# 2012_BALISE_CARTE_RECEPTEUR.net
KiCad netlist of a schematic drawn in Altium Designer
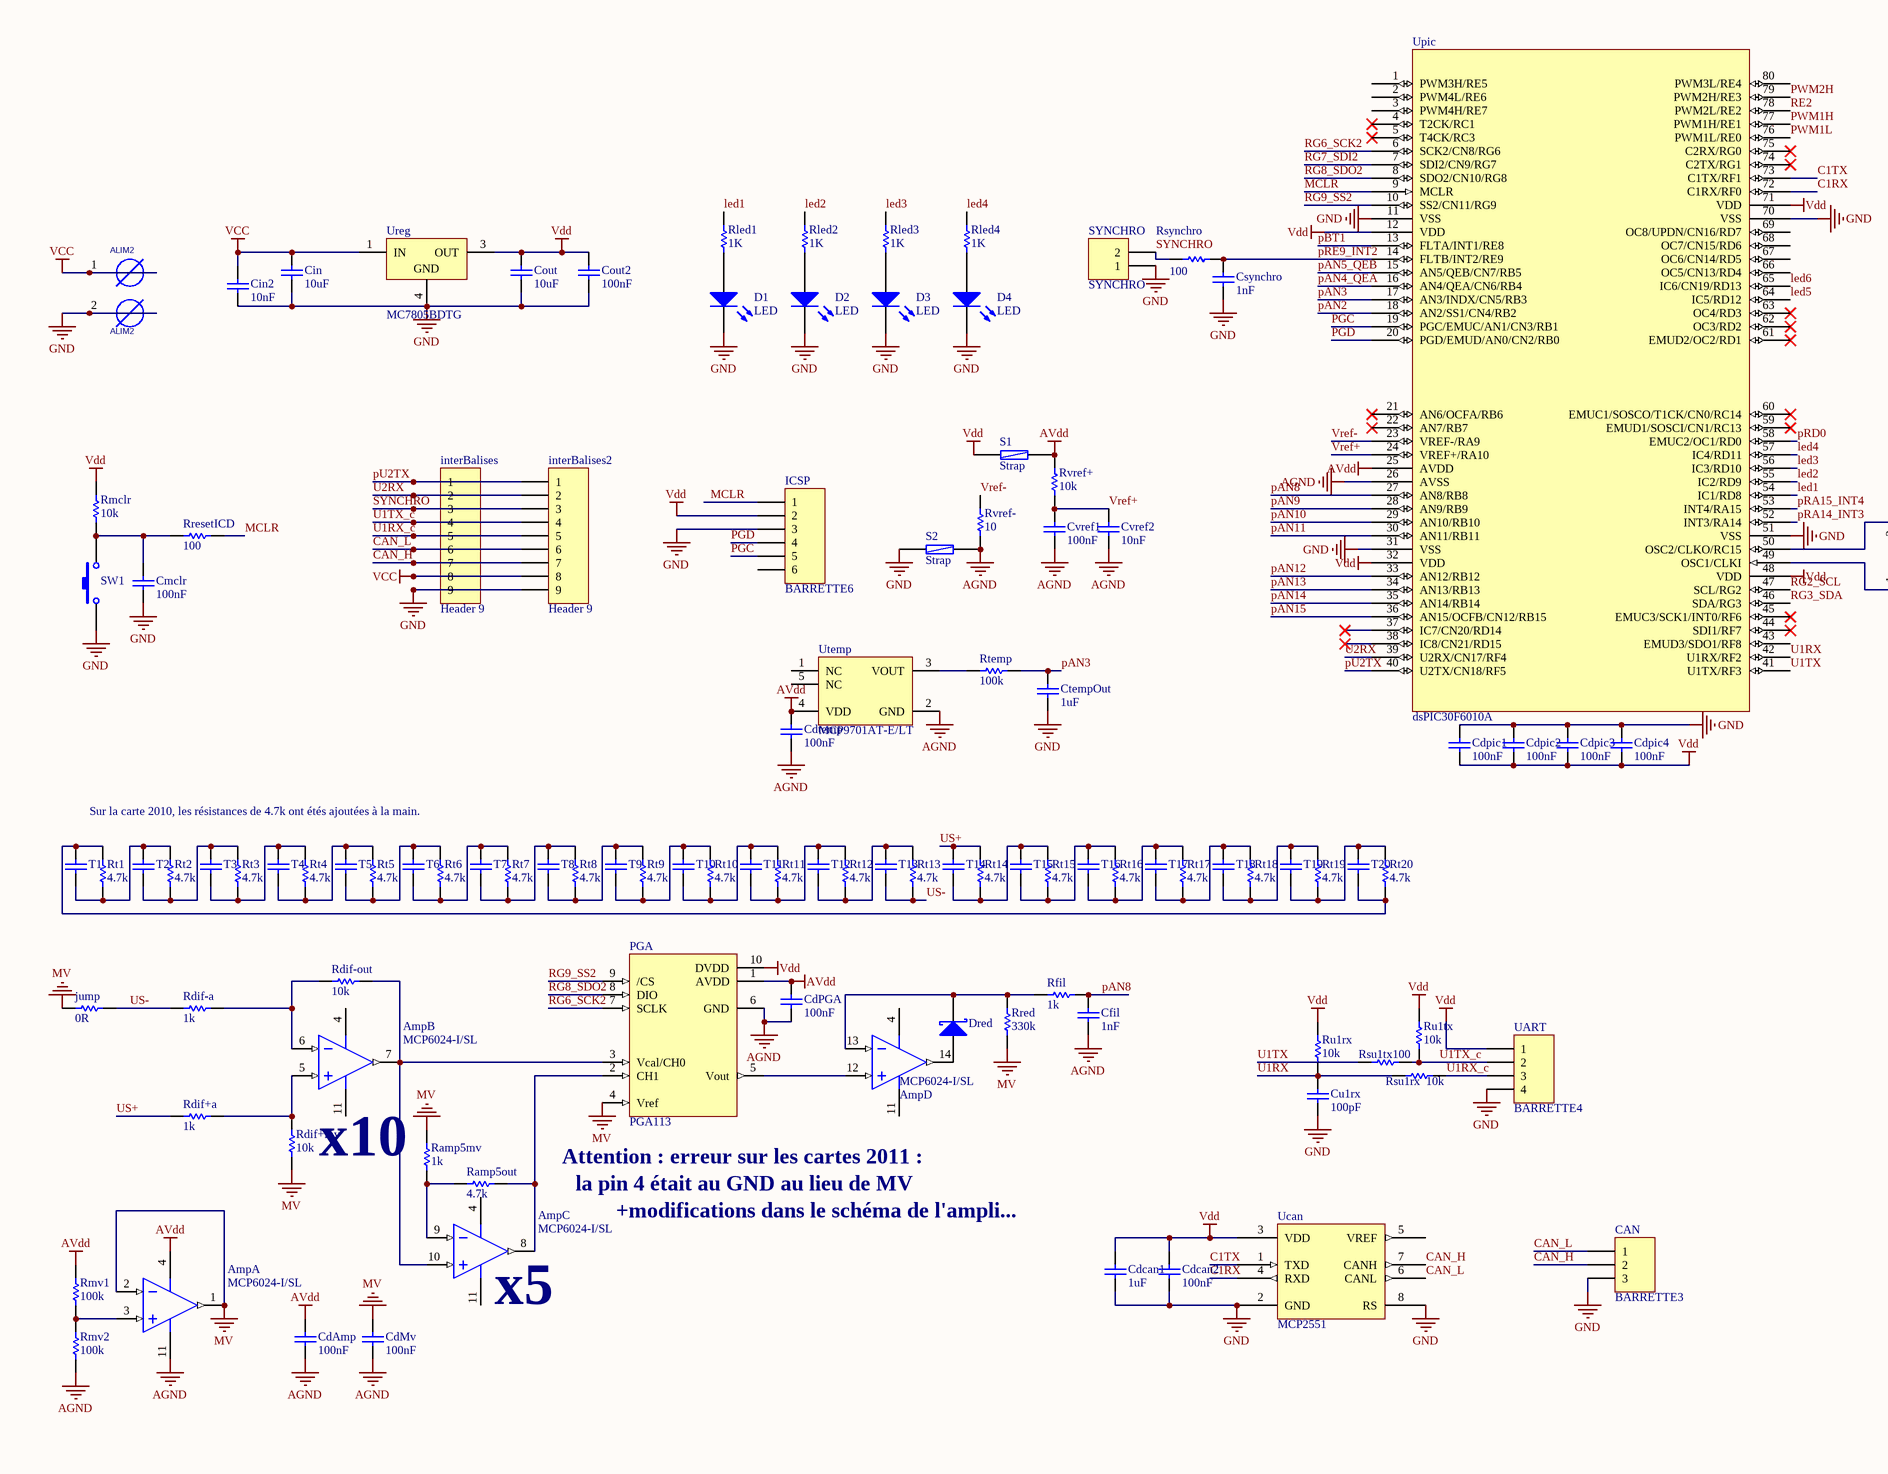
[diagram p0: 2012_BALISE_CARTE_RECEPTEUR.SchDoc, left]
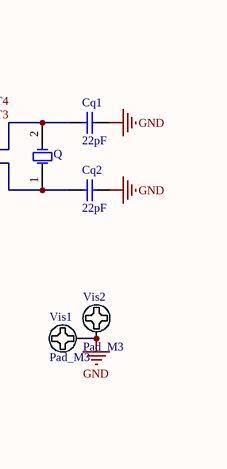
[diagram p1: 2012_BALISE_CARTE_RECEPTEUR.SchDoc, middle]
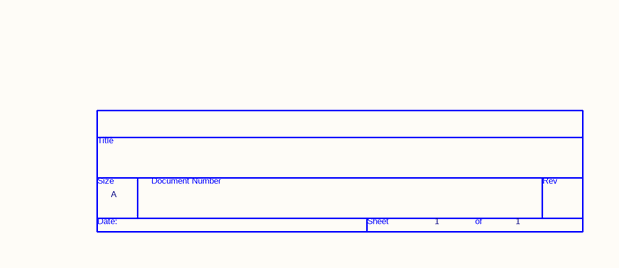
[diagram p2: 2012_BALISE_CARTE_RECEPTEUR.SchDoc, right]

(export (version "E")
  (design (tool "Eeschema 10.0.6"))
  (components
    (comp (ref "*")
      (value "TitleBlock0")
      (fields (field (name "PAGE COUNT") "1") (field (name "PAGE NUMBER") "1") (field (name "PAGE SIZE") "A"))
      (libsource (lib "*") (part "TitleBlock0"))
    )
    (comp (ref "ALIM2") (value "ALIM2") (footprint "BORNIER2") (libsource (lib "*") (part "BORNIER2")))
    (comp (ref "Amp")
      (value "MCP6024-I/SL")
      (footprint "SO14_N")
      (description "Rail-to-Rail Input/Output, 10 MHz Operational Amplifier, 14-Pin SOIC, Industrial Temperature")
      (fields (field (name "PUBLISHER") "Altium Limited"))
      (libsource (lib "Circuit intégré") (part "MCP6024-I/SL"))
    )
    (comp (ref "CAN")
      (value "BARRETTE3")
      (footprint "HE14_3")
      (description "Header, 3-Pin")
      (fields (field (name "PUBLISHER") "Altium Limited"))
      (libsource (lib "Connecteur") (part "BARRETTE3"))
    )
    (comp (ref "CdAmp")
      (value "100nF")
      (footprint "C0805_N")
      (description "Capacitor")
      (fields (field (name "PUBLISHER") "Altium Limited"))
      (libsource (lib "DG_Condensateur") (part "Capacitor"))
    )
    (comp (ref "Cdcan1")
      (value "1uF")
      (footprint "C1206_N")
      (description "Capacitor")
      (fields (field (name "PUBLISHER") "Altium Limited"))
      (libsource (lib "DG_Condensateur") (part "Capacitor"))
    )
    (comp (ref "Cdcan2")
      (value "100nF")
      (footprint "C0805_N")
      (description "Capacitor")
      (fields (field (name "PUBLISHER") "Altium Limited"))
      (libsource (lib "DG_Condensateur") (part "Capacitor"))
    )
    (comp (ref "CdMv")
      (value "100nF")
      (footprint "C0805_N")
      (description "Capacitor")
      (fields (field (name "PUBLISHER") "Altium Limited"))
      (libsource (lib "DG_Condensateur") (part "Capacitor"))
    )
    (comp (ref "CdPGA")
      (value "100nF")
      (footprint "C0805_N")
      (description "Capacitor")
      (fields (field (name "PUBLISHER") "Altium Limited"))
      (libsource (lib "DG_Condensateur") (part "Capacitor"))
    )
    (comp (ref "Cdpic1")
      (value "100nF")
      (footprint "C0805_N")
      (description "Capacitor")
      (fields (field (name "PUBLISHER") "Altium Limited"))
      (libsource (lib "DG_Condensateur") (part "Capacitor"))
    )
    (comp (ref "Cdpic2")
      (value "100nF")
      (footprint "C0805_N")
      (description "Capacitor")
      (fields (field (name "PUBLISHER") "Altium Limited"))
      (libsource (lib "DG_Condensateur") (part "Capacitor"))
    )
    (comp (ref "Cdpic3")
      (value "100nF")
      (footprint "C0805_N")
      (description "Capacitor")
      (fields (field (name "PUBLISHER") "Altium Limited"))
      (libsource (lib "DG_Condensateur") (part "Capacitor"))
    )
    (comp (ref "Cdpic4")
      (value "100nF")
      (footprint "C0805_N")
      (description "Capacitor")
      (fields (field (name "PUBLISHER") "Altium Limited"))
      (libsource (lib "DG_Condensateur") (part "Capacitor"))
    )
    (comp (ref "Cdtemp")
      (value "100nF")
      (footprint "C0805_N")
      (description "Capacitor")
      (fields (field (name "PUBLISHER") "Altium Limited"))
      (libsource (lib "DG_Condensateur") (part "Capacitor"))
    )
    (comp (ref "Cfil")
      (value "1nF")
      (footprint "C0805_N")
      (description "Capacitor")
      (fields (field (name "PUBLISHER") "Altium Limited"))
      (libsource (lib "DG_Condensateur") (part "Capacitor"))
    )
    (comp (ref "Cin")
      (value "10uF")
      (footprint "C1206_N")
      (description "Capacitor")
      (fields (field (name "PUBLISHER") "Altium Limited"))
      (libsource (lib "DG_Condensateur") (part "Capacitor"))
    )
    (comp (ref "Cin2")
      (value "10nF")
      (footprint "C0805_N")
      (description "Capacitor")
      (fields (field (name "PUBLISHER") "Altium Limited"))
      (libsource (lib "DG_Condensateur") (part "Capacitor"))
    )
    (comp (ref "Cmclr")
      (value "100nF")
      (footprint "C0805_N")
      (description "Capacitor")
      (fields (field (name "PUBLISHER") "Altium Limited"))
      (libsource (lib "DG_Condensateur") (part "Capacitor"))
    )
    (comp (ref "Cout")
      (value "10uF")
      (footprint "C1206_N")
      (description "Capacitor")
      (fields (field (name "PUBLISHER") "Altium Limited"))
      (libsource (lib "DG_Condensateur") (part "Capacitor"))
    )
    (comp (ref "Cout2")
      (value "100nF")
      (footprint "C0805_N")
      (description "Capacitor")
      (fields (field (name "PUBLISHER") "Altium Limited"))
      (libsource (lib "DG_Condensateur") (part "Capacitor"))
    )
    (comp (ref "Cq1")
      (value "22pF")
      (footprint "C0805_N")
      (description "Capacitor")
      (fields (field (name "PUBLISHER") "Altium Limited"))
      (libsource (lib "DG_Condensateur") (part "Capacitor"))
    )
    (comp (ref "Cq2")
      (value "22pF")
      (footprint "C0805_N")
      (description "Capacitor")
      (fields (field (name "PUBLISHER") "Altium Limited"))
      (libsource (lib "DG_Condensateur") (part "Capacitor"))
    )
    (comp (ref "Csynchro")
      (value "1nF")
      (footprint "C0805_N")
      (description "Capacitor")
      (fields (field (name "PUBLISHER") "Altium Limited"))
      (libsource (lib "DG_Condensateur") (part "Capacitor"))
    )
    (comp (ref "CtempOut")
      (value "1uF")
      (footprint "C0805_N")
      (description "Capacitor")
      (fields (field (name "PUBLISHER") "Altium Limited"))
      (libsource (lib "DG_Condensateur") (part "Capacitor"))
    )
    (comp (ref "Cu1rx")
      (value "100pF")
      (footprint "C0805_N")
      (description "Capacitor")
      (fields (field (name "PUBLISHER") "Altium Limited"))
      (libsource (lib "DG_Condensateur") (part "Capacitor"))
    )
    (comp (ref "Cvref1")
      (value "100nF")
      (footprint "C0805_N")
      (description "Capacitor")
      (fields (field (name "PUBLISHER") "Altium Limited"))
      (libsource (lib "DG_Condensateur") (part "Capacitor"))
    )
    (comp (ref "Cvref2")
      (value "10nF")
      (footprint "C0805_N")
      (description "Capacitor")
      (fields (field (name "PUBLISHER") "Altium Limited"))
      (libsource (lib "DG_Condensateur") (part "Capacitor"))
    )
    (comp (ref "D1")
      (value "LED")
      (footprint "LED_0805")
      (description "Typical LED")
      (fields (field (name "PUBLISHER") "Altium Limited"))
      (libsource (lib "DG_LED") (part "LED"))
    )
    (comp (ref "D2")
      (value "LED")
      (footprint "LED_0805")
      (description "Typical LED")
      (fields (field (name "PUBLISHER") "Altium Limited"))
      (libsource (lib "DG_LED") (part "LED"))
    )
    (comp (ref "D3")
      (value "LED")
      (footprint "LED_0805")
      (description "Typical LED")
      (fields (field (name "PUBLISHER") "Altium Limited"))
      (libsource (lib "DG_LED") (part "LED"))
    )
    (comp (ref "D4")
      (value "LED")
      (footprint "LED_0805")
      (description "Typical LED")
      (fields (field (name "PUBLISHER") "Altium Limited"))
      (libsource (lib "DG_LED") (part "LED"))
    )
    (comp (ref "Dred")
      (value "Diode Shottky BAT54")
      (footprint "SOT23-3N")
      (description "BAT54 - DIODE, SCHOTTKY, SOT-23")
      (fields (field (name "MANUFACTURER PART NUMBER") "BAT54"))
      (libsource (lib "_ROBOT") (part "Diode Shottky BAT54"))
    )
    (comp (ref "ICSP")
      (value "BARRETTE6")
      (footprint "HE14_6")
      (description "Header, 6-Pin")
      (fields (field (name "PUBLISHER") "Altium Limited"))
      (libsource (lib "Connecteur") (part "BARRETTE6"))
    )
    (comp (ref "interBalises")
      (value "Header 9")
      (footprint "HDR1X9")
      (description "Header, 9-Pin")
      (fields (field (name "PUBLISHER") "Altium Limited"))
      (libsource (lib "DG_Connecteur") (part "Header 9"))
    )
    (comp (ref "interBalises2")
      (value "Header 9")
      (footprint "HDR1X9")
      (description "Header, 9-Pin")
      (fields (field (name "PUBLISHER") "Altium Limited"))
      (libsource (lib "DG_Connecteur") (part "Header 9"))
    )
    (comp (ref "jump")
      (value "0R")
      (footprint "R0603_N")
      (description "Resistor")
      (fields (field (name "PUBLISHER") "Altium Limited"))
      (libsource (lib "DG_Resistance") (part "Resistor"))
    )
    (comp (ref "PGA")
      (value "PGA113")
      (footprint "MSOP-UN10_N")
      (description "Programmable Gain Amplifier")
      (libsource (lib "Circuit intégré") (part "PGA113"))
    )
    (comp (ref "Q")
      (value "QU")
      (footprint "HC49US")
      (description "Crystal Oscillator")
      (fields (field (name "PUBLISHER") "Altium Limited"))
      (libsource (lib "miniprojet") (part "QUARTZ_DROIT_BAS_PROFIL"))
    )
    (comp (ref "Ramp5mv")
      (value "1k")
      (footprint "R1206_N")
      (description "Resistor")
      (fields (field (name "PUBLISHER") "Altium Limited"))
      (libsource (lib "DG_Resistance") (part "Resistor"))
    )
    (comp (ref "Ramp5out")
      (value "4.7k")
      (footprint "R1206_N")
      (description "Resistor")
      (fields (field (name "PUBLISHER") "Altium Limited"))
      (libsource (lib "DG_Resistance") (part "Resistor"))
    )
    (comp (ref "Rdif+a")
      (value "1k")
      (footprint "R1206_N")
      (description "Resistor")
      (fields (field (name "PUBLISHER") "Altium Limited"))
      (libsource (lib "DG_Resistance") (part "Resistor"))
    )
    (comp (ref "Rdif+mv")
      (value "10k")
      (footprint "R1206_N")
      (description "Resistor")
      (fields (field (name "PUBLISHER") "Altium Limited"))
      (libsource (lib "DG_Resistance") (part "Resistor"))
    )
    (comp (ref "Rdif-a")
      (value "1k")
      (footprint "R1206_N")
      (description "Resistor")
      (fields (field (name "PUBLISHER") "Altium Limited"))
      (libsource (lib "DG_Resistance") (part "Resistor"))
    )
    (comp (ref "Rdif-out")
      (value "10k")
      (footprint "R1206_N")
      (description "Resistor")
      (fields (field (name "PUBLISHER") "Altium Limited"))
      (libsource (lib "DG_Resistance") (part "Resistor"))
    )
    (comp (ref "Rfil")
      (value "1k")
      (footprint "R1206_N")
      (description "Resistor")
      (fields (field (name "PUBLISHER") "Altium Limited"))
      (libsource (lib "DG_Resistance") (part "Resistor"))
    )
    (comp (ref "Rled1")
      (value "1K")
      (footprint "R1206_N")
      (description "Resistor")
      (fields (field (name "PUBLISHER") "Altium Limited"))
      (libsource (lib "DG_Resistance") (part "Resistor"))
    )
    (comp (ref "Rled2")
      (value "1K")
      (footprint "R1206_N")
      (description "Resistor")
      (fields (field (name "PUBLISHER") "Altium Limited"))
      (libsource (lib "DG_Resistance") (part "Resistor"))
    )
    (comp (ref "Rled3")
      (value "1K")
      (footprint "R1206_N")
      (description "Resistor")
      (fields (field (name "PUBLISHER") "Altium Limited"))
      (libsource (lib "DG_Resistance") (part "Resistor"))
    )
    (comp (ref "Rled4")
      (value "1K")
      (footprint "R1206_N")
      (description "Resistor")
      (fields (field (name "PUBLISHER") "Altium Limited"))
      (libsource (lib "DG_Resistance") (part "Resistor"))
    )
    (comp (ref "Rmclr")
      (value "10k")
      (footprint "R1206_N")
      (description "Resistor")
      (fields (field (name "PUBLISHER") "Altium Limited"))
      (libsource (lib "DG_Resistance") (part "Resistor"))
    )
    (comp (ref "Rmv1")
      (value "100k")
      (footprint "R1206_N")
      (description "Resistor")
      (fields (field (name "PUBLISHER") "Altium Limited"))
      (libsource (lib "DG_Resistance") (part "Resistor"))
    )
    (comp (ref "Rmv2")
      (value "100k")
      (footprint "R1206_N")
      (description "Resistor")
      (fields (field (name "PUBLISHER") "Altium Limited"))
      (libsource (lib "DG_Resistance") (part "Resistor"))
    )
    (comp (ref "Rred")
      (value "330k")
      (footprint "R1206_N")
      (description "Resistor")
      (fields (field (name "PUBLISHER") "Altium Limited"))
      (libsource (lib "DG_Resistance") (part "Resistor"))
    )
    (comp (ref "RresetICD")
      (value "100")
      (footprint "R1206_N")
      (description "Resistor")
      (fields (field (name "PUBLISHER") "Altium Limited"))
      (libsource (lib "DG_Resistance") (part "Resistor"))
    )
    (comp (ref "Rsu1rx")
      (value "10k")
      (footprint "R1206_N")
      (description "Resistor")
      (fields (field (name "PUBLISHER") "Altium Limited"))
      (libsource (lib "DG_Resistance") (part "Resistor"))
    )
    (comp (ref "Rsu1tx")
      (value "100")
      (footprint "R1206_N")
      (description "Resistor")
      (fields (field (name "PUBLISHER") "Altium Limited"))
      (libsource (lib "DG_Resistance") (part "Resistor"))
    )
    (comp (ref "Rsynchro")
      (value "100")
      (footprint "R1206_N")
      (description "Resistor")
      (fields (field (name "PUBLISHER") "Altium Limited"))
      (libsource (lib "_ROBOT") (part "Resistor"))
    )
    (comp (ref "Rt1")
      (value "4.7k")
      (footprint "R1206_N")
      (description "Resistor")
      (fields (field (name "PUBLISHER") "Altium Limited"))
      (libsource (lib "DG_Resistance") (part "Resistor"))
    )
    (comp (ref "Rt2")
      (value "4.7k")
      (footprint "R1206_N")
      (description "Resistor")
      (fields (field (name "PUBLISHER") "Altium Limited"))
      (libsource (lib "DG_Resistance") (part "Resistor"))
    )
    (comp (ref "Rt3")
      (value "4.7k")
      (footprint "R1206_N")
      (description "Resistor")
      (fields (field (name "PUBLISHER") "Altium Limited"))
      (libsource (lib "DG_Resistance") (part "Resistor"))
    )
    (comp (ref "Rt4")
      (value "4.7k")
      (footprint "R1206_N")
      (description "Resistor")
      (fields (field (name "PUBLISHER") "Altium Limited"))
      (libsource (lib "DG_Resistance") (part "Resistor"))
    )
    (comp (ref "Rt5")
      (value "4.7k")
      (footprint "R1206_N")
      (description "Resistor")
      (fields (field (name "PUBLISHER") "Altium Limited"))
      (libsource (lib "DG_Resistance") (part "Resistor"))
    )
    (comp (ref "Rt6")
      (value "4.7k")
      (footprint "R1206_N")
      (description "Resistor")
      (fields (field (name "PUBLISHER") "Altium Limited"))
      (libsource (lib "DG_Resistance") (part "Resistor"))
    )
    (comp (ref "Rt7")
      (value "4.7k")
      (footprint "R1206_N")
      (description "Resistor")
      (fields (field (name "PUBLISHER") "Altium Limited"))
      (libsource (lib "DG_Resistance") (part "Resistor"))
    )
    (comp (ref "Rt8")
      (value "4.7k")
      (footprint "R1206_N")
      (description "Resistor")
      (fields (field (name "PUBLISHER") "Altium Limited"))
      (libsource (lib "DG_Resistance") (part "Resistor"))
    )
    (comp (ref "Rt9")
      (value "4.7k")
      (footprint "R1206_N")
      (description "Resistor")
      (fields (field (name "PUBLISHER") "Altium Limited"))
      (libsource (lib "DG_Resistance") (part "Resistor"))
    )
    (comp (ref "Rt10")
      (value "4.7k")
      (footprint "R1206_N")
      (description "Resistor")
      (fields (field (name "PUBLISHER") "Altium Limited"))
      (libsource (lib "DG_Resistance") (part "Resistor"))
    )
    (comp (ref "Rt11")
      (value "4.7k")
      (footprint "R1206_N")
      (description "Resistor")
      (fields (field (name "PUBLISHER") "Altium Limited"))
      (libsource (lib "DG_Resistance") (part "Resistor"))
    )
    (comp (ref "Rt12")
      (value "4.7k")
      (footprint "R1206_N")
      (description "Resistor")
      (fields (field (name "PUBLISHER") "Altium Limited"))
      (libsource (lib "DG_Resistance") (part "Resistor"))
    )
    (comp (ref "Rt13")
      (value "4.7k")
      (footprint "R1206_N")
      (description "Resistor")
      (fields (field (name "PUBLISHER") "Altium Limited"))
      (libsource (lib "DG_Resistance") (part "Resistor"))
    )
    (comp (ref "Rt14")
      (value "4.7k")
      (footprint "R1206_N")
      (description "Resistor")
      (fields (field (name "PUBLISHER") "Altium Limited"))
      (libsource (lib "DG_Resistance") (part "Resistor"))
    )
    (comp (ref "Rt15")
      (value "4.7k")
      (footprint "R1206_N")
      (description "Resistor")
      (fields (field (name "PUBLISHER") "Altium Limited"))
      (libsource (lib "DG_Resistance") (part "Resistor"))
    )
    (comp (ref "Rt16")
      (value "4.7k")
      (footprint "R1206_N")
      (description "Resistor")
      (fields (field (name "PUBLISHER") "Altium Limited"))
      (libsource (lib "DG_Resistance") (part "Resistor"))
    )
    (comp (ref "Rt17")
      (value "4.7k")
      (footprint "R1206_N")
      (description "Resistor")
      (fields (field (name "PUBLISHER") "Altium Limited"))
      (libsource (lib "DG_Resistance") (part "Resistor"))
    )
    (comp (ref "Rt18")
      (value "4.7k")
      (footprint "R1206_N")
      (description "Resistor")
      (fields (field (name "PUBLISHER") "Altium Limited"))
      (libsource (lib "DG_Resistance") (part "Resistor"))
    )
    (comp (ref "Rt19")
      (value "4.7k")
      (footprint "R1206_N")
      (description "Resistor")
      (fields (field (name "PUBLISHER") "Altium Limited"))
      (libsource (lib "DG_Resistance") (part "Resistor"))
    )
    (comp (ref "Rt20")
      (value "4.7k")
      (footprint "R1206_N")
      (description "Resistor")
      (fields (field (name "PUBLISHER") "Altium Limited"))
      (libsource (lib "DG_Resistance") (part "Resistor"))
    )
    (comp (ref "Rtemp")
      (value "100k")
      (footprint "R1206_N")
      (description "Resistor")
      (fields (field (name "PUBLISHER") "Altium Limited"))
      (libsource (lib "DG_Resistance") (part "Resistor"))
    )
    (comp (ref "Ru1rx")
      (value "10k")
      (footprint "R1206_N")
      (description "Resistor")
      (fields (field (name "PUBLISHER") "Altium Limited"))
      (libsource (lib "DG_Resistance") (part "Resistor"))
    )
    (comp (ref "Ru1tx")
      (value "10k")
      (footprint "R1206_N")
      (description "Resistor")
      (fields (field (name "PUBLISHER") "Altium Limited"))
      (libsource (lib "DG_Resistance") (part "Resistor"))
    )
    (comp (ref "Rvref+")
      (value "10k")
      (footprint "R1206_N")
      (description "Resistor")
      (fields (field (name "PUBLISHER") "Altium Limited"))
      (libsource (lib "DG_Resistance") (part "Resistor"))
    )
    (comp (ref "Rvref-")
      (value "10")
      (footprint "R1206_N")
      (description "Resistor")
      (fields (field (name "PUBLISHER") "Altium Limited"))
      (libsource (lib "DG_Resistance") (part "Resistor"))
    )
    (comp (ref "S1")
      (value "Strap")
      (footprint "R0805_N")
      (description "Fuse")
      (fields (field (name "PUBLISHER") "Altium Limited"))
      (libsource (lib "_ROBOT") (part "Fusible_SMD"))
    )
    (comp (ref "S2")
      (value "Strap")
      (footprint "R0805_N")
      (description "Fuse")
      (fields (field (name "PUBLISHER") "Altium Limited"))
      (libsource (lib "_ROBOT") (part "Fusible_SMD"))
    )
    (comp (ref "SW1")
      (value "SW_Pushbutton_6x6mm_Vertical")
      (footprint "Switch 6x6 Vertical")
      (description "Switch tactil 6mm x 6mm Vertical")
      (fields (field (name "PUBLISHER") "Damien Guitton"))
      (libsource (lib "DG_Interrupteur") (part "SW_Pushbutton_6x6mm_Vertical"))
    )
    (comp (ref "SYNCHRO")
      (value "SYNCHRO")
      (footprint "Robot2010:HEADER2")
      (description "Header, 2-Pin")
      (fields (field (name "PUBLISHER") "Altium Limited"))
      (libsource (lib "Robot2010") (part "BARRETTE2"))
    )
    (comp (ref "T1")
      (value "40kHz")
      (footprint "MA40S4R/S Transducteur US - 3D_mi_carte")
      (description "Capacitor")
      (fields (field (name "PUBLISHER") "Altium Limited"))
      (libsource (lib "_ROBOT") (part "Condensateur"))
    )
    (comp (ref "T2")
      (value "40kHz")
      (footprint "MA40S4R/S Transducteur US - 3D_mi_carte")
      (description "Capacitor")
      (fields (field (name "PUBLISHER") "Altium Limited"))
      (libsource (lib "_ROBOT") (part "Condensateur"))
    )
    (comp (ref "T3")
      (value "40kHz")
      (footprint "MA40S4R/S Transducteur US - 3D_mi_carte")
      (description "Capacitor")
      (fields (field (name "PUBLISHER") "Altium Limited"))
      (libsource (lib "_ROBOT") (part "Condensateur"))
    )
    (comp (ref "T4")
      (value "40kHz")
      (footprint "MA40S4R/S Transducteur US - 3D_mi_carte")
      (description "Capacitor")
      (fields (field (name "PUBLISHER") "Altium Limited"))
      (libsource (lib "_ROBOT") (part "Condensateur"))
    )
    (comp (ref "T5")
      (value "40kHz")
      (footprint "MA40S4R/S Transducteur US - 3D_mi_carte")
      (description "Capacitor")
      (fields (field (name "PUBLISHER") "Altium Limited"))
      (libsource (lib "_ROBOT") (part "Condensateur"))
    )
    (comp (ref "T6")
      (value "40kHz")
      (footprint "MA40S4R/S Transducteur US - 3D_mi_carte")
      (description "Capacitor")
      (fields (field (name "PUBLISHER") "Altium Limited"))
      (libsource (lib "_ROBOT") (part "Condensateur"))
    )
    (comp (ref "T7")
      (value "40kHz")
      (footprint "MA40S4R/S Transducteur US - 3D_mi_carte")
      (description "Capacitor")
      (fields (field (name "PUBLISHER") "Altium Limited"))
      (libsource (lib "_ROBOT") (part "Condensateur"))
    )
    (comp (ref "T8")
      (value "40kHz")
      (footprint "MA40S4R/S Transducteur US - 3D_mi_carte")
      (description "Capacitor")
      (fields (field (name "PUBLISHER") "Altium Limited"))
      (libsource (lib "_ROBOT") (part "Condensateur"))
    )
    (comp (ref "T9")
      (value "40kHz")
      (footprint "MA40S4R/S Transducteur US - 3D_mi_carte")
      (description "Capacitor")
      (fields (field (name "PUBLISHER") "Altium Limited"))
      (libsource (lib "_ROBOT") (part "Condensateur"))
    )
    (comp (ref "T10")
      (value "40kHz")
      (footprint "MA40S4R/S Transducteur US - 3D_mi_carte")
      (description "Capacitor")
      (fields (field (name "PUBLISHER") "Altium Limited"))
      (libsource (lib "_ROBOT") (part "Condensateur"))
    )
    (comp (ref "T11")
      (value "40kHz")
      (footprint "MA40S4R/S Transducteur US - 3D_mi_carte")
      (description "Capacitor")
      (fields (field (name "PUBLISHER") "Altium Limited"))
      (libsource (lib "_ROBOT") (part "Condensateur"))
    )
    (comp (ref "T12")
      (value "40kHz")
      (footprint "MA40S4R/S Transducteur US - 3D_mi_carte")
      (description "Capacitor")
      (fields (field (name "PUBLISHER") "Altium Limited"))
      (libsource (lib "_ROBOT") (part "Condensateur"))
    )
    (comp (ref "T13")
      (value "40kHz")
      (footprint "MA40S4R/S Transducteur US - 3D_mi_carte")
      (description "Capacitor")
      (fields (field (name "PUBLISHER") "Altium Limited"))
      (libsource (lib "_ROBOT") (part "Condensateur"))
    )
    (comp (ref "T14")
      (value "40kHz")
      (footprint "MA40S4R/S Transducteur US - 3D_mi_carte")
      (description "Capacitor")
      (fields (field (name "PUBLISHER") "Altium Limited"))
      (libsource (lib "_ROBOT") (part "Condensateur"))
    )
    (comp (ref "T15")
      (value "40kHz")
      (footprint "MA40S4R/S Transducteur US - 3D_mi_carte")
      (description "Capacitor")
      (fields (field (name "PUBLISHER") "Altium Limited"))
      (libsource (lib "_ROBOT") (part "Condensateur"))
    )
    (comp (ref "T16")
      (value "40kHz")
      (footprint "MA40S4R/S Transducteur US - 3D_mi_carte")
      (description "Capacitor")
      (fields (field (name "PUBLISHER") "Altium Limited"))
      (libsource (lib "_ROBOT") (part "Condensateur"))
    )
    (comp (ref "T17")
      (value "40kHz")
      (footprint "MA40S4R/S Transducteur US - 3D_mi_carte")
      (description "Capacitor")
      (fields (field (name "PUBLISHER") "Altium Limited"))
      (libsource (lib "_ROBOT") (part "Condensateur"))
    )
    (comp (ref "T18")
      (value "40kHz")
      (footprint "MA40S4R/S Transducteur US - 3D_mi_carte")
      (description "Capacitor")
      (fields (field (name "PUBLISHER") "Altium Limited"))
      (libsource (lib "_ROBOT") (part "Condensateur"))
    )
    (comp (ref "T19")
      (value "40kHz")
      (footprint "MA40S4R/S Transducteur US - 3D_mi_carte")
      (description "Capacitor")
      (fields (field (name "PUBLISHER") "Altium Limited"))
      (libsource (lib "_ROBOT") (part "Condensateur"))
    )
    (comp (ref "T20")
      (value "40kHz")
      (footprint "MA40S4R/S Transducteur US - 3D_mi_carte")
      (description "Capacitor")
      (fields (field (name "PUBLISHER") "Altium Limited"))
      (libsource (lib "_ROBOT") (part "Condensateur"))
    )
    (comp (ref "UART")
      (value "BARRETTE4")
      (footprint "HE14_4")
      (description "Header, 4-Pin")
      (fields (field (name "PUBLISHER") "Altium Limited"))
      (libsource (lib "Connecteur") (part "BARRETTE4"))
    )
    (comp (ref "Ucan")
      (value "MCP2551")
      (footprint "SO8_N")
      (description "High Speed Can Transceiver")
      (fields (field (name "PUBLISHER") "Altium Limited"))
      (libsource (lib "Microchip Interface Line Transceiver") (part "MCP2551"))
    )
    (comp (ref "Upic")
      (value "dsPIC30F6010A")
      (footprint "TQFP80_N")
      (description "High-Performance, 16-bit Digital Signal Controllers")
      (libsource (lib "DG_Microcontroleur") (part "dsPIC30F6010A"))
    )
    (comp (ref "Ureg")
      (value "MC7805BDTG")
      (footprint "369A-13")
      (description "Three-Terminal Positive Voltage Regulator")
      (fields (field (name "PUBLISHER") "Altium Limited"))
      (libsource (lib "ON Semi Power Mgt Voltage Regulator") (part "MC7805ACD2T"))
    )
    (comp (ref "Utemp")
      (value "MCP9701AT-E/LT")
      (footprint "SC70-LT5_N")
      (description "Low-Power Linear Active Thermistor IC, 5-Pin SC-70, Extended Temperature, Tape and Reel")
      (fields (field (name "PUBLISHER") "Altium Limited"))
      (libsource (lib "Microchip Thermal Management") (part "MCP9701AT-E/LT"))
    )
    (comp (ref "Vis1")
      (value "Pad_M3")
      (footprint "M3x6mm")
      (description "Vis M3 X 6mm _TORX_Tête 6mm")
      (fields (field (name "PUBLISHER") "Damien Guitton"))
      (libsource (lib "DG_Mecanique") (part "Vis M3 X 6mm _TORX_Tête 6mm"))
    )
    (comp (ref "Vis2")
      (value "Pad_M3")
      (footprint "M3x6mm")
      (description "Vis M3 X 6mm _TORX_Tête 6mm")
      (fields (field (name "PUBLISHER") "Damien Guitton"))
      (libsource (lib "DG_Mecanique") (part "Vis M3 X 6mm _TORX_Tête 6mm"))
    )
  )
  (nets
    (net (code "1") (name "/C1RX") (class "Default")
      (node (ref "Ucan") (pin "4") (pinfunction "RXD_4") (pintype "output"))
      (node (ref "Upic") (pin "72") (pinfunction "C1RX/RF0_72") (pintype "bidirectional"))
    )
    (net (code "2") (name "/C1TX") (class "Default")
      (node (ref "Ucan") (pin "1") (pinfunction "TXD_1") (pintype "input"))
      (node (ref "Upic") (pin "73") (pinfunction "C1TX/RF1_73") (pintype "bidirectional"))
    )
    (net (code "3") (name "/CAN_H") (class "Default")
      (node (ref "CAN") (pin "2") (pinfunction "2_2") (pintype "passive"))
      (node (ref "Ucan") (pin "7") (pinfunction "CANH_7") (pintype "output"))
      (node (ref "interBalises") (pin "7") (pinfunction "7_7") (pintype "passive"))
      (node (ref "interBalises2") (pin "7") (pinfunction "7_7") (pintype "passive"))
    )
    (net (code "4") (name "/CAN_L") (class "Default")
      (node (ref "CAN") (pin "1") (pinfunction "1_1") (pintype "passive"))
      (node (ref "Ucan") (pin "6") (pinfunction "CANL_6") (pintype "output"))
      (node (ref "interBalises") (pin "6") (pinfunction "6_6") (pintype "passive"))
      (node (ref "interBalises2") (pin "6") (pinfunction "6_6") (pintype "passive"))
    )
    (net (code "5") (name "/MCLR") (class "Default")
      (node (ref "ICSP") (pin "1") (pinfunction "1_1") (pintype "passive"))
      (node (ref "RresetICD") (pin "1") (pinfunction "1_1") (pintype "passive"))
      (node (ref "Upic") (pin "9") (pinfunction "MCLR_9") (pintype "input"))
    )
    (net (code "6") (name "/PGC") (class "Default")
      (node (ref "ICSP") (pin "5") (pinfunction "5_5") (pintype "passive"))
      (node (ref "Upic") (pin "19") (pinfunction "PGC/EMUC/AN1/CN3/RB1_19") (pintype "bidirectional"))
    )
    (net (code "7") (name "/PGD") (class "Default")
      (node (ref "ICSP") (pin "4") (pinfunction "4_4") (pintype "passive"))
      (node (ref "Upic") (pin "20") (pinfunction "PGD/EMUD/AN0/CN2/RB0_20") (pintype "bidirectional"))
    )
    (net (code "8") (name "/PWM1H") (class "Default")
      (node (ref "Upic") (pin "77") (pinfunction "PWM1H/RE1_77") (pintype "bidirectional"))
    )
    (net (code "9") (name "/PWM1L") (class "Default")
      (node (ref "Upic") (pin "76") (pinfunction "PWM1L/RE0_76") (pintype "bidirectional"))
    )
    (net (code "10") (name "/PWM2H") (class "Default")
      (node (ref "Upic") (pin "79") (pinfunction "PWM2H/RE3_79") (pintype "bidirectional"))
    )
    (net (code "11") (name "/RE2") (class "Default")
      (node (ref "Upic") (pin "78") (pinfunction "PWM2L/RE2_78") (pintype "bidirectional"))
    )
    (net (code "12") (name "/RG2_SCL") (class "Default")
      (node (ref "Upic") (pin "47") (pinfunction "SCL/RG2_47") (pintype "bidirectional"))
    )
    (net (code "13") (name "/RG3_SDA") (class "Default")
      (node (ref "Upic") (pin "46") (pinfunction "SDA/RG3_46") (pintype "bidirectional"))
    )
    (net (code "14") (name "/RG6_SCK2") (class "Default")
      (node (ref "PGA") (pin "7") (pinfunction "SCLK_7") (pintype "input"))
      (node (ref "Upic") (pin "6") (pinfunction "SCK2/CN8/RG6_6") (pintype "bidirectional"))
    )
    (net (code "15") (name "/RG7_SDI2") (class "Default")
      (node (ref "Upic") (pin "7") (pinfunction "SDI2/CN9/RG7_7") (pintype "bidirectional"))
    )
    (net (code "16") (name "/RG8_SDO2") (class "Default")
      (node (ref "PGA") (pin "8") (pinfunction "DIO_8") (pintype "input"))
      (node (ref "Upic") (pin "8") (pinfunction "SDO2/CN10/RG8_8") (pintype "bidirectional"))
    )
    (net (code "17") (name "/RG9_SS2") (class "Default")
      (node (ref "PGA") (pin "9") (pinfunction "/CS_9") (pintype "input"))
      (node (ref "Upic") (pin "10") (pinfunction "SS2/CN11/RG9_10") (pintype "bidirectional"))
    )
    (net (code "18") (name "/SYNCHRO") (class "Default")
      (node (ref "Rsynchro") (pin "1") (pinfunction "1_1") (pintype "passive"))
      (node (ref "SYNCHRO") (pin "2") (pinfunction "2_2") (pintype "passive"))
      (node (ref "interBalises") (pin "3") (pinfunction "3_3") (pintype "passive"))
      (node (ref "interBalises2") (pin "3") (pinfunction "3_3") (pintype "passive"))
    )
    (net (code "19") (name "/U1RX") (class "Default")
      (node (ref "Cu1rx") (pin "2") (pinfunction "2_2") (pintype "passive"))
      (node (ref "Rsu1rx") (pin "2") (pinfunction "2_2") (pintype "passive"))
      (node (ref "Ru1rx") (pin "1") (pinfunction "1_1") (pintype "passive"))
      (node (ref "Upic") (pin "42") (pinfunction "U1RX/RF2_42") (pintype "bidirectional"))
    )
    (net (code "20") (name "/U1RX_c") (class "Default")
      (node (ref "Rsu1rx") (pin "1") (pinfunction "1_1") (pintype "passive"))
      (node (ref "UART") (pin "3") (pinfunction "3_3") (pintype "passive"))
      (node (ref "interBalises") (pin "5") (pinfunction "5_5") (pintype "passive"))
      (node (ref "interBalises2") (pin "5") (pinfunction "5_5") (pintype "passive"))
    )
    (net (code "21") (name "/U1TX") (class "Default")
      (node (ref "Rsu1tx") (pin "2") (pinfunction "2_2") (pintype "passive"))
      (node (ref "Upic") (pin "41") (pinfunction "U1TX/RF3_41") (pintype "bidirectional"))
    )
    (net (code "22") (name "/U1TX_c") (class "Default")
      (node (ref "Rsu1tx") (pin "1") (pinfunction "1_1") (pintype "passive"))
      (node (ref "Ru1tx") (pin "1") (pinfunction "1_1") (pintype "passive"))
      (node (ref "UART") (pin "2") (pinfunction "2_2") (pintype "passive"))
      (node (ref "interBalises") (pin "4") (pinfunction "4_4") (pintype "passive"))
      (node (ref "interBalises2") (pin "4") (pinfunction "4_4") (pintype "passive"))
    )
    (net (code "23") (name "/U2RX") (class "Default")
      (node (ref "Upic") (pin "39") (pinfunction "U2RX/CN17/RF4_39") (pintype "bidirectional"))
      (node (ref "interBalises") (pin "2") (pinfunction "2_2") (pintype "passive"))
      (node (ref "interBalises2") (pin "2") (pinfunction "2_2") (pintype "passive"))
    )
    (net (code "24") (name "/US+") (class "Default")
      (node (ref "Rdif+a") (pin "2") (pinfunction "2_2") (pintype "passive"))
      (node (ref "Rt14") (pin "1") (pinfunction "1_1") (pintype "passive"))
      (node (ref "T14") (pin "2") (pinfunction "2_2") (pintype "passive"))
    )
    (net (code "25") (name "/US-") (class "Default")
      (node (ref "Rdif-a") (pin "2") (pinfunction "2_2") (pintype "passive"))
      (node (ref "Rt13") (pin "2") (pinfunction "2_2") (pintype "passive"))
      (node (ref "T13") (pin "1") (pinfunction "1_1") (pintype "passive"))
      (node (ref "jump") (pin "2") (pinfunction "2_2") (pintype "passive"))
    )
    (net (code "26") (name "/Vref+") (class "Default")
      (node (ref "Cvref1") (pin "2") (pinfunction "2_2") (pintype "passive"))
      (node (ref "Cvref2") (pin "2") (pinfunction "2_2") (pintype "passive"))
      (node (ref "Rvref+") (pin "1") (pinfunction "1_1") (pintype "passive"))
      (node (ref "Upic") (pin "24") (pinfunction "VREF+/RA10_24") (pintype "bidirectional"))
    )
    (net (code "27") (name "/Vref-") (class "Default")
      (node (ref "Rvref-") (pin "2") (pinfunction "2_2") (pintype "passive"))
      (node (ref "Upic") (pin "23") (pinfunction "VREF-/RA9_23") (pintype "bidirectional"))
    )
    (net (code "28") (name "/led1") (class "Default")
      (node (ref "Rled1") (pin "2") (pinfunction "2_2") (pintype "passive"))
      (node (ref "Upic") (pin "54") (pinfunction "IC1/RD8_54") (pintype "bidirectional"))
    )
    (net (code "29") (name "/led2") (class "Default")
      (node (ref "Rled2") (pin "2") (pinfunction "2_2") (pintype "passive"))
      (node (ref "Upic") (pin "55") (pinfunction "IC2/RD9_55") (pintype "bidirectional"))
    )
    (net (code "30") (name "/led3") (class "Default")
      (node (ref "Rled3") (pin "2") (pinfunction "2_2") (pintype "passive"))
      (node (ref "Upic") (pin "56") (pinfunction "IC3/RD10_56") (pintype "bidirectional"))
    )
    (net (code "31") (name "/led4") (class "Default")
      (node (ref "Rled4") (pin "2") (pinfunction "2_2") (pintype "passive"))
      (node (ref "Upic") (pin "57") (pinfunction "IC4/RD11_57") (pintype "bidirectional"))
    )
    (net (code "32") (name "/led5") (class "Default")
      (node (ref "Upic") (pin "64") (pinfunction "IC5/RD12_64") (pintype "bidirectional"))
    )
    (net (code "33") (name "/led6") (class "Default")
      (node (ref "Upic") (pin "65") (pinfunction "IC6/CN19/RD13_65") (pintype "bidirectional"))
    )
    (net (code "34") (name "/pAN2") (class "Default")
      (node (ref "Upic") (pin "18") (pinfunction "AN2/SS1/CN4/RB2_18") (pintype "bidirectional"))
    )
    (net (code "35") (name "/pAN3") (class "Default")
      (node (ref "CtempOut") (pin "2") (pinfunction "2_2") (pintype "passive"))
      (node (ref "Rtemp") (pin "1") (pinfunction "1_1") (pintype "passive"))
      (node (ref "Upic") (pin "17") (pinfunction "AN3/INDX/CN5/RB3_17") (pintype "bidirectional"))
    )
    (net (code "36") (name "/pAN4_QEA") (class "Default")
      (node (ref "Upic") (pin "16") (pinfunction "AN4/QEA/CN6/RB4_16") (pintype "bidirectional"))
    )
    (net (code "37") (name "/pAN5_QEB") (class "Default")
      (node (ref "Upic") (pin "15") (pinfunction "AN5/QEB/CN7/RB5_15") (pintype "bidirectional"))
    )
    (net (code "38") (name "/pAN8") (class "Default")
      (node (ref "Cfil") (pin "2") (pinfunction "2_2") (pintype "passive"))
      (node (ref "Rfil") (pin "2") (pinfunction "2_2") (pintype "passive"))
      (node (ref "Upic") (pin "27") (pinfunction "AN8/RB8_27") (pintype "bidirectional"))
    )
    (net (code "39") (name "/pAN9") (class "Default")
      (node (ref "Upic") (pin "28") (pinfunction "AN9/RB9_28") (pintype "bidirectional"))
    )
    (net (code "40") (name "/pAN10") (class "Default")
      (node (ref "Upic") (pin "29") (pinfunction "AN10/RB10_29") (pintype "bidirectional"))
    )
    (net (code "41") (name "/pAN11") (class "Default")
      (node (ref "Upic") (pin "30") (pinfunction "AN11/RB11_30") (pintype "bidirectional"))
    )
    (net (code "42") (name "/pAN12") (class "Default")
      (node (ref "Upic") (pin "33") (pinfunction "AN12/RB12_33") (pintype "bidirectional"))
    )
    (net (code "43") (name "/pAN13") (class "Default")
      (node (ref "Upic") (pin "34") (pinfunction "AN13/RB13_34") (pintype "bidirectional"))
    )
    (net (code "44") (name "/pAN14") (class "Default")
      (node (ref "Upic") (pin "35") (pinfunction "AN14/RB14_35") (pintype "bidirectional"))
    )
    (net (code "45") (name "/pAN15") (class "Default")
      (node (ref "Upic") (pin "36") (pinfunction "AN15/OCFB/CN12/RB15_36") (pintype "bidirectional"))
    )
    (net (code "46") (name "/pBT1") (class "Default")
      (node (ref "Upic") (pin "13") (pinfunction "FLTA/INT1/RE8_13") (pintype "bidirectional"))
    )
    (net (code "47") (name "/pRA14_INT3") (class "Default")
      (node (ref "Upic") (pin "52") (pinfunction "INT3/RA14_52") (pintype "bidirectional"))
    )
    (net (code "48") (name "/pRA15_INT4") (class "Default")
      (node (ref "Upic") (pin "53") (pinfunction "INT4/RA15_53") (pintype "bidirectional"))
    )
    (net (code "49") (name "/pRD0") (class "Default")
      (node (ref "Upic") (pin "58") (pinfunction "EMUC2/OC1/RD0_58") (pintype "bidirectional"))
    )
    (net (code "50") (name "/pRE9_INT2") (class "Default")
      (node (ref "Csynchro") (pin "1") (pinfunction "1_1") (pintype "passive"))
      (node (ref "Rsynchro") (pin "2") (pinfunction "2_2") (pintype "passive"))
      (node (ref "Upic") (pin "14") (pinfunction "FLTB/INT2/RE9_14") (pintype "bidirectional"))
    )
    (net (code "51") (name "/pU2TX") (class "Default")
      (node (ref "Upic") (pin "40") (pinfunction "U2TX/CN18/RF5_40") (pintype "bidirectional"))
      (node (ref "interBalises") (pin "1") (pinfunction "1_1") (pintype "passive"))
      (node (ref "interBalises2") (pin "1") (pinfunction "1_1") (pintype "passive"))
    )
    (net (code "52") (name "AGND") (class "Default")
      (node (ref "Amp") (pin "11") (pinfunction "VSS_11") (pintype "power_in"))
      (node (ref "CdAmp") (pin "1") (pinfunction "1_1") (pintype "passive"))
      (node (ref "CdMv") (pin "1") (pinfunction "1_1") (pintype "passive"))
      (node (ref "CdPGA") (pin "1") (pinfunction "1_1") (pintype "passive"))
      (node (ref "Cdtemp") (pin "1") (pinfunction "1_1") (pintype "passive"))
      (node (ref "Cfil") (pin "1") (pinfunction "1_1") (pintype "passive"))
      (node (ref "Cvref1") (pin "1") (pinfunction "1_1") (pintype "passive"))
      (node (ref "Cvref2") (pin "1") (pinfunction "1_1") (pintype "passive"))
      (node (ref "PGA") (pin "6") (pinfunction "GND_6") (pintype "power_in"))
      (node (ref "Rmv2") (pin "1") (pinfunction "1_1") (pintype "passive"))
      (node (ref "Rvref-") (pin "1") (pinfunction "1_1") (pintype "passive"))
      (node (ref "S2") (pin "2") (pinfunction "2_2") (pintype "passive"))
      (node (ref "Upic") (pin "26") (pinfunction "AVSS_26") (pintype "power_in"))
      (node (ref "Utemp") (pin "2") (pinfunction "GND_2") (pintype "power_in"))
    )
    (net (code "53") (name "AVdd") (class "Default")
      (node (ref "Amp") (pin "4") (pinfunction "VDD_4") (pintype "power_in"))
      (node (ref "CdAmp") (pin "2") (pinfunction "2_2") (pintype "passive"))
      (node (ref "CdPGA") (pin "2") (pinfunction "2_2") (pintype "passive"))
      (node (ref "Cdtemp") (pin "2") (pinfunction "2_2") (pintype "passive"))
      (node (ref "PGA") (pin "1") (pinfunction "AVDD_1") (pintype "power_in"))
      (node (ref "Rmv1") (pin "2") (pinfunction "2_2") (pintype "passive"))
      (node (ref "Rvref+") (pin "2") (pinfunction "2_2") (pintype "passive"))
      (node (ref "S1") (pin "2") (pinfunction "2_2") (pintype "passive"))
      (node (ref "Upic") (pin "25") (pinfunction "AVDD_25") (pintype "power_in"))
      (node (ref "Utemp") (pin "4") (pinfunction "VDD_4") (pintype "power_in"))
    )
    (net (code "54") (name "GND") (class "Default")
      (node (ref "ALIM2") (pin "2") (pinfunction "B2_2") (pintype "passive"))
      (node (ref "CAN") (pin "3") (pinfunction "3_3") (pintype "passive"))
      (node (ref "Cdcan1") (pin "1") (pinfunction "1_1") (pintype "passive"))
      (node (ref "Cdcan2") (pin "1") (pinfunction "1_1") (pintype "passive"))
      (node (ref "Cdpic1") (pin "2") (pinfunction "2_2") (pintype "passive"))
      (node (ref "Cdpic2") (pin "2") (pinfunction "2_2") (pintype "passive"))
      (node (ref "Cdpic3") (pin "2") (pinfunction "2_2") (pintype "passive"))
      (node (ref "Cdpic4") (pin "2") (pinfunction "2_2") (pintype "passive"))
      (node (ref "Cin") (pin "1") (pinfunction "1_1") (pintype "passive"))
      (node (ref "Cin2") (pin "1") (pinfunction "1_1") (pintype "passive"))
      (node (ref "Cmclr") (pin "1") (pinfunction "1_1") (pintype "passive"))
      (node (ref "Cout") (pin "1") (pinfunction "1_1") (pintype "passive"))
      (node (ref "Cout2") (pin "1") (pinfunction "1_1") (pintype "passive"))
      (node (ref "Cq1") (pin "2") (pinfunction "2_2") (pintype "passive"))
      (node (ref "Cq2") (pin "2") (pinfunction "2_2") (pintype "passive"))
      (node (ref "Csynchro") (pin "2") (pinfunction "2_2") (pintype "passive"))
      (node (ref "CtempOut") (pin "1") (pinfunction "1_1") (pintype "passive"))
      (node (ref "Cu1rx") (pin "1") (pinfunction "1_1") (pintype "passive"))
      (node (ref "D1") (pin "2") (pinfunction "2_2") (pintype "passive"))
      (node (ref "D2") (pin "2") (pinfunction "2_2") (pintype "passive"))
      (node (ref "D3") (pin "2") (pinfunction "2_2") (pintype "passive"))
      (node (ref "D4") (pin "2") (pinfunction "2_2") (pintype "passive"))
      (node (ref "ICSP") (pin "3") (pinfunction "3_3") (pintype "passive"))
      (node (ref "S2") (pin "1") (pinfunction "1_1") (pintype "passive"))
      (node (ref "SW1") (pin "1") (pinfunction "1_1") (pintype "passive"))
      (node (ref "SYNCHRO") (pin "1") (pinfunction "1_1") (pintype "passive"))
      (node (ref "UART") (pin "4") (pinfunction "4_4") (pintype "passive"))
      (node (ref "Ucan") (pin "2") (pinfunction "GND_2") (pintype "power_in"))
      (node (ref "Ucan") (pin "8") (pinfunction "RS_8") (pintype "passive"))
      (node (ref "Upic") (pin "11") (pinfunction "VSS_11") (pintype "power_in"))
      (node (ref "Upic") (pin "31") (pinfunction "VSS_31") (pintype "power_in"))
      (node (ref "Upic") (pin "51") (pinfunction "VSS_51") (pintype "power_in"))
      (node (ref "Upic") (pin "70") (pinfunction "VSS_70") (pintype "power_in"))
      (node (ref "Ureg") (pin "4") (pinfunction "GND_4") (pintype "power_in"))
      (node (ref "Vis1") (pin "1") (pinfunction "1_1") (pintype "passive"))
      (node (ref "Vis2") (pin "1") (pinfunction "1_1") (pintype "passive"))
      (node (ref "interBalises") (pin "9") (pinfunction "9_9") (pintype "passive"))
      (node (ref "interBalises2") (pin "9") (pinfunction "9_9") (pintype "passive"))
    )
    (net (code "55") (name "MV") (class "Default")
      (node (ref "Amp") (pin "1") (pinfunction "VOUTA_1") (pintype "output"))
      (node (ref "Amp") (pin "2") (pinfunction "VINA-_2") (pintype "input"))
      (node (ref "CdMv") (pin "2") (pinfunction "2_2") (pintype "passive"))
      (node (ref "PGA") (pin "4") (pinfunction "Vref_4") (pintype "input"))
      (node (ref "Ramp5mv") (pin "2") (pinfunction "2_2") (pintype "passive"))
      (node (ref "Rdif+mv") (pin "1") (pinfunction "1_1") (pintype "passive"))
      (node (ref "Rred") (pin "2") (pinfunction "2_2") (pintype "passive"))
      (node (ref "jump") (pin "1") (pinfunction "1_1") (pintype "passive"))
    )
    (net (code "56") (name "Net-(AmpA-VINA+)") (class "Default")
      (node (ref "Amp") (pin "3") (pinfunction "VINA+_3") (pintype "input"))
      (node (ref "Rmv1") (pin "1") (pinfunction "1_1") (pintype "passive"))
      (node (ref "Rmv2") (pin "2") (pinfunction "2_2") (pintype "passive"))
    )
    (net (code "57") (name "Net-(AmpB-VINB+)") (class "Default")
      (node (ref "Amp") (pin "5") (pinfunction "VINB+_5") (pintype "input"))
      (node (ref "Rdif+a") (pin "1") (pinfunction "1_1") (pintype "passive"))
      (node (ref "Rdif+mv") (pin "2") (pinfunction "2_2") (pintype "passive"))
    )
    (net (code "58") (name "Net-(AmpB-VINB-)") (class "Default")
      (node (ref "Amp") (pin "6") (pinfunction "VINB-_6") (pintype "input"))
      (node (ref "Rdif-a") (pin "1") (pinfunction "1_1") (pintype "passive"))
      (node (ref "Rdif-out") (pin "2") (pinfunction "2_2") (pintype "passive"))
    )
    (net (code "59") (name "Net-(AmpB-VOUTB)") (class "Default")
      (node (ref "Amp") (pin "10") (pinfunction "VINC+_10") (pintype "input"))
      (node (ref "Amp") (pin "7") (pinfunction "VOUTB_7") (pintype "output"))
      (node (ref "PGA") (pin "3") (pinfunction "Vcal/CH0_3") (pintype "input"))
      (node (ref "Rdif-out") (pin "1") (pinfunction "1_1") (pintype "passive"))
    )
    (net (code "60") (name "Net-(AmpC-VINC-)") (class "Default")
      (node (ref "Amp") (pin "9") (pinfunction "VINC-_9") (pintype "input"))
      (node (ref "Ramp5mv") (pin "1") (pinfunction "1_1") (pintype "passive"))
      (node (ref "Ramp5out") (pin "2") (pinfunction "2_2") (pintype "passive"))
    )
    (net (code "61") (name "Net-(AmpC-VOUTC)") (class "Default")
      (node (ref "Amp") (pin "8") (pinfunction "VOUTC_8") (pintype "output"))
      (node (ref "PGA") (pin "2") (pinfunction "CH1_2") (pintype "input"))
      (node (ref "Ramp5out") (pin "1") (pinfunction "1_1") (pintype "passive"))
    )
    (net (code "62") (name "Net-(AmpD-VIND+)") (class "Default")
      (node (ref "Amp") (pin "12") (pinfunction "VIND+_12") (pintype "input"))
      (node (ref "PGA") (pin "5") (pinfunction "Vout_5") (pintype "output"))
    )
    (net (code "63") (name "Net-(AmpD-VIND-)") (class "Default")
      (node (ref "Amp") (pin "13") (pinfunction "VIND-_13") (pintype "input"))
      (node (ref "Dred") (pin "3") (pinfunction "K_3") (pintype "passive"))
      (node (ref "Rfil") (pin "1") (pinfunction "1_1") (pintype "passive"))
      (node (ref "Rred") (pin "1") (pinfunction "1_1") (pintype "passive"))
    )
    (net (code "64") (name "Net-(AmpD-VOUTD)") (class "Default")
      (node (ref "Amp") (pin "14") (pinfunction "VOUTD_14") (pintype "output"))
      (node (ref "Dred") (pin "1") (pinfunction "A_1") (pintype "passive"))
    )
    (net (code "65") (name "Net-(Cmclr-Pad2)") (class "Default")
      (node (ref "Cmclr") (pin "2") (pinfunction "2_2") (pintype "passive"))
      (node (ref "Rmclr") (pin "1") (pinfunction "1_1") (pintype "passive"))
      (node (ref "RresetICD") (pin "2") (pinfunction "2_2") (pintype "passive"))
      (node (ref "SW1") (pin "3") (pinfunction "3_3") (pintype "passive"))
    )
    (net (code "66") (name "Net-(D1-Pad1)") (class "Default")
      (node (ref "D1") (pin "1") (pinfunction "1_1") (pintype "passive"))
      (node (ref "Rled1") (pin "1") (pinfunction "1_1") (pintype "passive"))
    )
    (net (code "67") (name "Net-(D2-Pad1)") (class "Default")
      (node (ref "D2") (pin "1") (pinfunction "1_1") (pintype "passive"))
      (node (ref "Rled2") (pin "1") (pinfunction "1_1") (pintype "passive"))
    )
    (net (code "68") (name "Net-(D3-Pad1)") (class "Default")
      (node (ref "D3") (pin "1") (pinfunction "1_1") (pintype "passive"))
      (node (ref "Rled3") (pin "1") (pinfunction "1_1") (pintype "passive"))
    )
    (net (code "69") (name "Net-(D4-Pad1)") (class "Default")
      (node (ref "D4") (pin "1") (pinfunction "1_1") (pintype "passive"))
      (node (ref "Rled4") (pin "1") (pinfunction "1_1") (pintype "passive"))
    )
    (net (code "70") (name "Net-(Q-OSC1)") (class "Default")
      (node (ref "Cq2") (pin "1") (pinfunction "1_1") (pintype "passive"))
      (node (ref "Q") (pin "1") (pinfunction "OSC1_1") (pintype "passive"))
      (node (ref "Upic") (pin "49") (pinfunction "OSC1/CLKI_49") (pintype "input"))
    )
    (net (code "71") (name "Net-(Q-OSC2)") (class "Default")
      (node (ref "Cq1") (pin "1") (pinfunction "1_1") (pintype "passive"))
      (node (ref "Q") (pin "2") (pinfunction "OSC2_2") (pintype "passive"))
      (node (ref "Upic") (pin "50") (pinfunction "OSC2/CLKO/RC15_50") (pintype "bidirectional"))
    )
    (net (code "72") (name "Net-(Rt1-Pad1)") (class "Default")
      (node (ref "Rt1") (pin "1") (pinfunction "1_1") (pintype "passive"))
      (node (ref "Rt20") (pin "2") (pinfunction "2_2") (pintype "passive"))
      (node (ref "T1") (pin "2") (pinfunction "2_2") (pintype "passive"))
      (node (ref "T20") (pin "1") (pinfunction "1_1") (pintype "passive"))
    )
    (net (code "73") (name "Net-(Rt1-Pad2)") (class "Default")
      (node (ref "Rt1") (pin "2") (pinfunction "2_2") (pintype "passive"))
      (node (ref "Rt2") (pin "1") (pinfunction "1_1") (pintype "passive"))
      (node (ref "T1") (pin "1") (pinfunction "1_1") (pintype "passive"))
      (node (ref "T2") (pin "2") (pinfunction "2_2") (pintype "passive"))
    )
    (net (code "74") (name "Net-(Rt2-Pad2)") (class "Default")
      (node (ref "Rt2") (pin "2") (pinfunction "2_2") (pintype "passive"))
      (node (ref "Rt3") (pin "1") (pinfunction "1_1") (pintype "passive"))
      (node (ref "T2") (pin "1") (pinfunction "1_1") (pintype "passive"))
      (node (ref "T3") (pin "2") (pinfunction "2_2") (pintype "passive"))
    )
    (net (code "75") (name "Net-(Rt3-Pad2)") (class "Default")
      (node (ref "Rt3") (pin "2") (pinfunction "2_2") (pintype "passive"))
      (node (ref "Rt4") (pin "1") (pinfunction "1_1") (pintype "passive"))
      (node (ref "T3") (pin "1") (pinfunction "1_1") (pintype "passive"))
      (node (ref "T4") (pin "2") (pinfunction "2_2") (pintype "passive"))
    )
    (net (code "76") (name "Net-(Rt4-Pad2)") (class "Default")
      (node (ref "Rt4") (pin "2") (pinfunction "2_2") (pintype "passive"))
      (node (ref "Rt5") (pin "1") (pinfunction "1_1") (pintype "passive"))
      (node (ref "T4") (pin "1") (pinfunction "1_1") (pintype "passive"))
      (node (ref "T5") (pin "2") (pinfunction "2_2") (pintype "passive"))
    )
    (net (code "77") (name "Net-(Rt5-Pad2)") (class "Default")
      (node (ref "Rt5") (pin "2") (pinfunction "2_2") (pintype "passive"))
      (node (ref "Rt6") (pin "1") (pinfunction "1_1") (pintype "passive"))
      (node (ref "T5") (pin "1") (pinfunction "1_1") (pintype "passive"))
      (node (ref "T6") (pin "2") (pinfunction "2_2") (pintype "passive"))
    )
    (net (code "78") (name "Net-(Rt6-Pad2)") (class "Default")
      (node (ref "Rt6") (pin "2") (pinfunction "2_2") (pintype "passive"))
      (node (ref "Rt7") (pin "1") (pinfunction "1_1") (pintype "passive"))
      (node (ref "T6") (pin "1") (pinfunction "1_1") (pintype "passive"))
      (node (ref "T7") (pin "2") (pinfunction "2_2") (pintype "passive"))
    )
    (net (code "79") (name "Net-(Rt7-Pad2)") (class "Default")
      (node (ref "Rt7") (pin "2") (pinfunction "2_2") (pintype "passive"))
      (node (ref "Rt8") (pin "1") (pinfunction "1_1") (pintype "passive"))
      (node (ref "T7") (pin "1") (pinfunction "1_1") (pintype "passive"))
      (node (ref "T8") (pin "2") (pinfunction "2_2") (pintype "passive"))
    )
    (net (code "80") (name "Net-(Rt8-Pad2)") (class "Default")
      (node (ref "Rt8") (pin "2") (pinfunction "2_2") (pintype "passive"))
      (node (ref "Rt9") (pin "1") (pinfunction "1_1") (pintype "passive"))
      (node (ref "T8") (pin "1") (pinfunction "1_1") (pintype "passive"))
      (node (ref "T9") (pin "2") (pinfunction "2_2") (pintype "passive"))
    )
    (net (code "81") (name "Net-(Rt10-Pad1)") (class "Default")
      (node (ref "Rt10") (pin "1") (pinfunction "1_1") (pintype "passive"))
      (node (ref "Rt9") (pin "2") (pinfunction "2_2") (pintype "passive"))
      (node (ref "T10") (pin "2") (pinfunction "2_2") (pintype "passive"))
      (node (ref "T9") (pin "1") (pinfunction "1_1") (pintype "passive"))
    )
    (net (code "82") (name "Net-(Rt10-Pad2)") (class "Default")
      (node (ref "Rt10") (pin "2") (pinfunction "2_2") (pintype "passive"))
      (node (ref "Rt11") (pin "1") (pinfunction "1_1") (pintype "passive"))
      (node (ref "T10") (pin "1") (pinfunction "1_1") (pintype "passive"))
      (node (ref "T11") (pin "2") (pinfunction "2_2") (pintype "passive"))
    )
    (net (code "83") (name "Net-(Rt11-Pad2)") (class "Default")
      (node (ref "Rt11") (pin "2") (pinfunction "2_2") (pintype "passive"))
      (node (ref "Rt12") (pin "1") (pinfunction "1_1") (pintype "passive"))
      (node (ref "T11") (pin "1") (pinfunction "1_1") (pintype "passive"))
      (node (ref "T12") (pin "2") (pinfunction "2_2") (pintype "passive"))
    )
    (net (code "84") (name "Net-(Rt12-Pad2)") (class "Default")
      (node (ref "Rt12") (pin "2") (pinfunction "2_2") (pintype "passive"))
      (node (ref "Rt13") (pin "1") (pinfunction "1_1") (pintype "passive"))
      (node (ref "T12") (pin "1") (pinfunction "1_1") (pintype "passive"))
      (node (ref "T13") (pin "2") (pinfunction "2_2") (pintype "passive"))
    )
    (net (code "85") (name "Net-(Rt14-Pad2)") (class "Default")
      (node (ref "Rt14") (pin "2") (pinfunction "2_2") (pintype "passive"))
      (node (ref "Rt15") (pin "1") (pinfunction "1_1") (pintype "passive"))
      (node (ref "T14") (pin "1") (pinfunction "1_1") (pintype "passive"))
      (node (ref "T15") (pin "2") (pinfunction "2_2") (pintype "passive"))
    )
    (net (code "86") (name "Net-(Rt15-Pad2)") (class "Default")
      (node (ref "Rt15") (pin "2") (pinfunction "2_2") (pintype "passive"))
      (node (ref "Rt16") (pin "1") (pinfunction "1_1") (pintype "passive"))
      (node (ref "T15") (pin "1") (pinfunction "1_1") (pintype "passive"))
      (node (ref "T16") (pin "2") (pinfunction "2_2") (pintype "passive"))
    )
    (net (code "87") (name "Net-(Rt16-Pad2)") (class "Default")
      (node (ref "Rt16") (pin "2") (pinfunction "2_2") (pintype "passive"))
      (node (ref "Rt17") (pin "1") (pinfunction "1_1") (pintype "passive"))
      (node (ref "T16") (pin "1") (pinfunction "1_1") (pintype "passive"))
      (node (ref "T17") (pin "2") (pinfunction "2_2") (pintype "passive"))
    )
    (net (code "88") (name "Net-(Rt17-Pad2)") (class "Default")
      (node (ref "Rt17") (pin "2") (pinfunction "2_2") (pintype "passive"))
      (node (ref "Rt18") (pin "1") (pinfunction "1_1") (pintype "passive"))
      (node (ref "T17") (pin "1") (pinfunction "1_1") (pintype "passive"))
      (node (ref "T18") (pin "2") (pinfunction "2_2") (pintype "passive"))
    )
    (net (code "89") (name "Net-(Rt18-Pad2)") (class "Default")
      (node (ref "Rt18") (pin "2") (pinfunction "2_2") (pintype "passive"))
      (node (ref "Rt19") (pin "1") (pinfunction "1_1") (pintype "passive"))
      (node (ref "T18") (pin "1") (pinfunction "1_1") (pintype "passive"))
      (node (ref "T19") (pin "2") (pinfunction "2_2") (pintype "passive"))
    )
    (net (code "90") (name "Net-(Rt19-Pad2)") (class "Default")
      (node (ref "Rt19") (pin "2") (pinfunction "2_2") (pintype "passive"))
      (node (ref "Rt20") (pin "1") (pinfunction "1_1") (pintype "passive"))
      (node (ref "T19") (pin "1") (pinfunction "1_1") (pintype "passive"))
      (node (ref "T20") (pin "2") (pinfunction "2_2") (pintype "passive"))
    )
    (net (code "91") (name "Net-(Utemp-VOUT)") (class "Default")
      (node (ref "Rtemp") (pin "2") (pinfunction "2_2") (pintype "passive"))
      (node (ref "Utemp") (pin "3") (pinfunction "VOUT_3") (pintype "power_in"))
    )
    (net (code "92") (name "VCC") (class "Default")
      (node (ref "ALIM2") (pin "1") (pinfunction "B1_1") (pintype "passive"))
      (node (ref "Cin") (pin "2") (pinfunction "2_2") (pintype "passive"))
      (node (ref "Cin2") (pin "2") (pinfunction "2_2") (pintype "passive"))
      (node (ref "Ureg") (pin "1") (pinfunction "IN_1") (pintype "power_in"))
      (node (ref "interBalises") (pin "8") (pinfunction "8_8") (pintype "passive"))
      (node (ref "interBalises2") (pin "8") (pinfunction "8_8") (pintype "passive"))
    )
    (net (code "93") (name "Vdd") (class "Default")
      (node (ref "Cdcan1") (pin "2") (pinfunction "2_2") (pintype "passive"))
      (node (ref "Cdcan2") (pin "2") (pinfunction "2_2") (pintype "passive"))
      (node (ref "Cdpic1") (pin "1") (pinfunction "1_1") (pintype "passive"))
      (node (ref "Cdpic2") (pin "1") (pinfunction "1_1") (pintype "passive"))
      (node (ref "Cdpic3") (pin "1") (pinfunction "1_1") (pintype "passive"))
      (node (ref "Cdpic4") (pin "1") (pinfunction "1_1") (pintype "passive"))
      (node (ref "Cout") (pin "2") (pinfunction "2_2") (pintype "passive"))
      (node (ref "Cout2") (pin "2") (pinfunction "2_2") (pintype "passive"))
      (node (ref "ICSP") (pin "2") (pinfunction "2_2") (pintype "passive"))
      (node (ref "PGA") (pin "10") (pinfunction "DVDD_10") (pintype "power_in"))
      (node (ref "Rmclr") (pin "2") (pinfunction "2_2") (pintype "passive"))
      (node (ref "Ru1rx") (pin "2") (pinfunction "2_2") (pintype "passive"))
      (node (ref "Ru1tx") (pin "2") (pinfunction "2_2") (pintype "passive"))
      (node (ref "S1") (pin "1") (pinfunction "1_1") (pintype "passive"))
      (node (ref "UART") (pin "1") (pinfunction "1_1") (pintype "passive"))
      (node (ref "Ucan") (pin "3") (pinfunction "VDD_3") (pintype "power_in"))
      (node (ref "Upic") (pin "12") (pinfunction "VDD_12") (pintype "power_in"))
      (node (ref "Upic") (pin "32") (pinfunction "VDD_32") (pintype "power_in"))
      (node (ref "Upic") (pin "48") (pinfunction "VDD_48") (pintype "power_in"))
      (node (ref "Upic") (pin "71") (pinfunction "VDD_71") (pintype "power_in"))
      (node (ref "Ureg") (pin "3") (pinfunction "OUT_3") (pintype "power_in"))
    )
    (net (code "94") (name "unconnected-(AmpB-VDD-Pad4)") (class "Default")
      (node (ref "Amp") (pin "4") (pinfunction "VDD_4") (pintype "power_in"))
    )
    (net (code "95") (name "unconnected-(AmpB-VSS-Pad11)") (class "Default")
      (node (ref "Amp") (pin "11") (pinfunction "VSS_11") (pintype "power_in"))
    )
    (net (code "96") (name "unconnected-(AmpC-VDD-Pad4)") (class "Default")
      (node (ref "Amp") (pin "4") (pinfunction "VDD_4") (pintype "power_in"))
    )
    (net (code "97") (name "unconnected-(AmpC-VSS-Pad11)") (class "Default")
      (node (ref "Amp") (pin "11") (pinfunction "VSS_11") (pintype "power_in"))
    )
    (net (code "98") (name "unconnected-(AmpD-VDD-Pad4)") (class "Default")
      (node (ref "Amp") (pin "4") (pinfunction "VDD_4") (pintype "power_in"))
    )
    (net (code "99") (name "unconnected-(AmpD-VSS-Pad11)") (class "Default")
      (node (ref "Amp") (pin "11") (pinfunction "VSS_11") (pintype "power_in"))
    )
    (net (code "100") (name "unconnected-(ICSP-Pad6)") (class "Default")
      (node (ref "ICSP") (pin "6") (pinfunction "6_6") (pintype "passive"))
    )
    (net (code "101") (name "unconnected-(Ucan-VREF-Pad5)") (class "Default")
      (node (ref "Ucan") (pin "5") (pinfunction "VREF_5") (pintype "output"))
    )
    (net (code "102") (name "unconnected-(Upic-AN6{slash}OCFA{slash}RB6-Pad21)") (class "Default")
      (node (ref "Upic") (pin "21") (pinfunction "AN6/OCFA/RB6_21") (pintype "bidirectional+no_connect"))
    )
    (net (code "103") (name "unconnected-(Upic-AN7{slash}RB7-Pad22)") (class "Default")
      (node (ref "Upic") (pin "22") (pinfunction "AN7/RB7_22") (pintype "bidirectional+no_connect"))
    )
    (net (code "104") (name "unconnected-(Upic-C2RX{slash}RG0-Pad75)") (class "Default")
      (node (ref "Upic") (pin "75") (pinfunction "C2RX/RG0_75") (pintype "bidirectional+no_connect"))
    )
    (net (code "105") (name "unconnected-(Upic-C2TX{slash}RG1-Pad74)") (class "Default")
      (node (ref "Upic") (pin "74") (pinfunction "C2TX/RG1_74") (pintype "bidirectional+no_connect"))
    )
    (net (code "106") (name "unconnected-(Upic-EMUC1{slash}SOSCO{slash}T1CK{slash}CN0{slash}RC14-Pad60)") (class "Default")
      (node (ref "Upic") (pin "60") (pinfunction "EMUC1/SOSCO/T1CK/CN0/RC14_60") (pintype "bidirectional+no_connect"))
    )
    (net (code "107") (name "unconnected-(Upic-EMUC3{slash}SCK1{slash}INT0{slash}RF6-Pad45)") (class "Default")
      (node (ref "Upic") (pin "45") (pinfunction "EMUC3/SCK1/INT0/RF6_45") (pintype "bidirectional+no_connect"))
    )
    (net (code "108") (name "unconnected-(Upic-EMUD1{slash}SOSCI{slash}CN1{slash}RC13-Pad59)") (class "Default")
      (node (ref "Upic") (pin "59") (pinfunction "EMUD1/SOSCI/CN1/RC13_59") (pintype "bidirectional+no_connect"))
    )
    (net (code "109") (name "unconnected-(Upic-EMUD2{slash}OC2{slash}RD1-Pad61)") (class "Default")
      (node (ref "Upic") (pin "61") (pinfunction "EMUD2/OC2/RD1_61") (pintype "bidirectional+no_connect"))
    )
    (net (code "110") (name "unconnected-(Upic-EMUD3{slash}SDO1{slash}RF8-Pad43)") (class "Default")
      (node (ref "Upic") (pin "43") (pinfunction "EMUD3/SDO1/RF8_43") (pintype "bidirectional"))
    )
    (net (code "111") (name "unconnected-(Upic-IC7{slash}CN20{slash}RD14-Pad37)") (class "Default")
      (node (ref "Upic") (pin "37") (pinfunction "IC7/CN20/RD14_37") (pintype "bidirectional+no_connect"))
    )
    (net (code "112") (name "unconnected-(Upic-IC8{slash}CN21{slash}RD15-Pad38)") (class "Default")
      (node (ref "Upic") (pin "38") (pinfunction "IC8/CN21/RD15_38") (pintype "bidirectional+no_connect"))
    )
    (net (code "113") (name "unconnected-(Upic-OC3{slash}RD2-Pad62)") (class "Default")
      (node (ref "Upic") (pin "62") (pinfunction "OC3/RD2_62") (pintype "bidirectional+no_connect"))
    )
    (net (code "114") (name "unconnected-(Upic-OC4{slash}RD3-Pad63)") (class "Default")
      (node (ref "Upic") (pin "63") (pinfunction "OC4/RD3_63") (pintype "bidirectional+no_connect"))
    )
    (net (code "115") (name "unconnected-(Upic-OC5{slash}CN13{slash}RD4-Pad66)") (class "Default")
      (node (ref "Upic") (pin "66") (pinfunction "OC5/CN13/RD4_66") (pintype "bidirectional"))
    )
    (net (code "116") (name "unconnected-(Upic-OC6{slash}CN14{slash}RD5-Pad67)") (class "Default")
      (node (ref "Upic") (pin "67") (pinfunction "OC6/CN14/RD5_67") (pintype "bidirectional"))
    )
    (net (code "117") (name "unconnected-(Upic-OC7{slash}CN15{slash}RD6-Pad68)") (class "Default")
      (node (ref "Upic") (pin "68") (pinfunction "OC7/CN15/RD6_68") (pintype "bidirectional"))
    )
    (net (code "118") (name "unconnected-(Upic-OC8{slash}UPDN{slash}CN16{slash}RD7-Pad69)") (class "Default")
      (node (ref "Upic") (pin "69") (pinfunction "OC8/UPDN/CN16/RD7_69") (pintype "bidirectional"))
    )
    (net (code "119") (name "unconnected-(Upic-PWM3H{slash}RE5-Pad1)") (class "Default")
      (node (ref "Upic") (pin "1") (pinfunction "PWM3H/RE5_1") (pintype "bidirectional"))
    )
    (net (code "120") (name "unconnected-(Upic-PWM3L{slash}RE4-Pad80)") (class "Default")
      (node (ref "Upic") (pin "80") (pinfunction "PWM3L/RE4_80") (pintype "bidirectional"))
    )
    (net (code "121") (name "unconnected-(Upic-PWM4H{slash}RE7-Pad3)") (class "Default")
      (node (ref "Upic") (pin "3") (pinfunction "PWM4H/RE7_3") (pintype "bidirectional"))
    )
    (net (code "122") (name "unconnected-(Upic-PWM4L{slash}RE6-Pad2)") (class "Default")
      (node (ref "Upic") (pin "2") (pinfunction "PWM4L/RE6_2") (pintype "bidirectional"))
    )
    (net (code "123") (name "unconnected-(Upic-SDI1{slash}RF7-Pad44)") (class "Default")
      (node (ref "Upic") (pin "44") (pinfunction "SDI1/RF7_44") (pintype "bidirectional+no_connect"))
    )
    (net (code "124") (name "unconnected-(Upic-T2CK{slash}RC1-Pad4)") (class "Default")
      (node (ref "Upic") (pin "4") (pinfunction "T2CK/RC1_4") (pintype "bidirectional+no_connect"))
    )
    (net (code "125") (name "unconnected-(Upic-T4CK{slash}RC3-Pad5)") (class "Default")
      (node (ref "Upic") (pin "5") (pinfunction "T4CK/RC3_5") (pintype "bidirectional+no_connect"))
    )
    (net (code "126") (name "unconnected-(Utemp-NC-Pad1)") (class "Default")
      (node (ref "Utemp") (pin "1") (pinfunction "NC_1") (pintype "passive"))
    )
    (net (code "127") (name "unconnected-(Utemp-NC-Pad5)") (class "Default")
      (node (ref "Utemp") (pin "5") (pinfunction "NC_5") (pintype "passive"))
    )
  )
)
